# Sheet3.net
KiCad netlist of a schematic drawn in Altium Designer
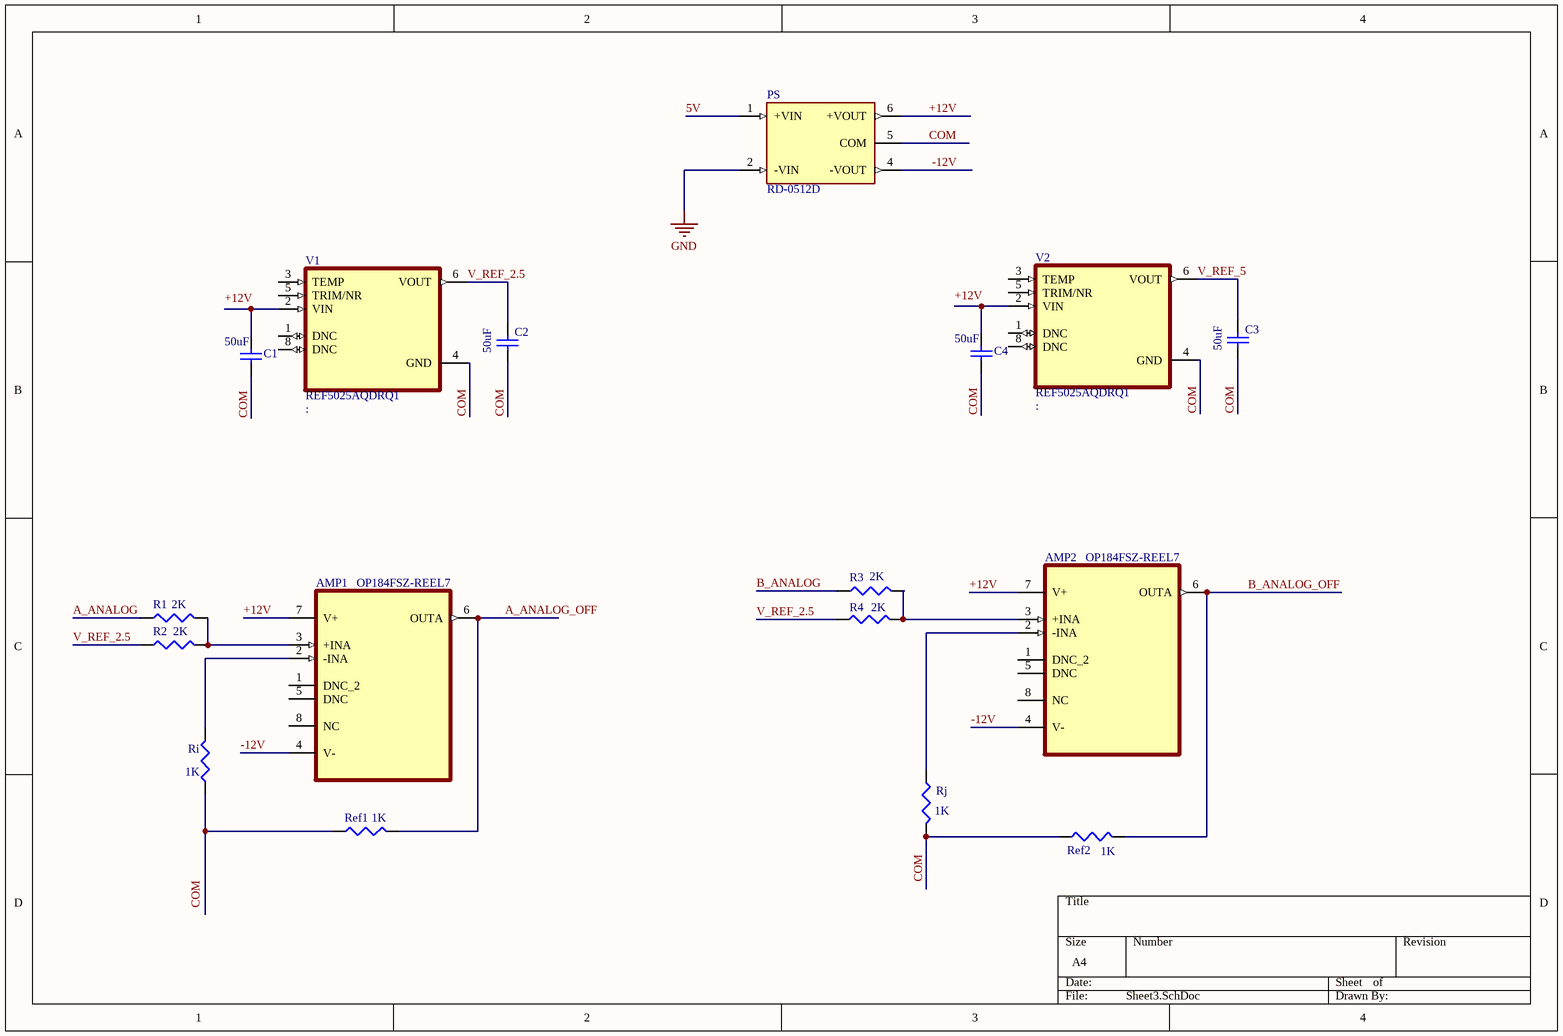
[diagram p0: Sheet3.SchDoc]

(export (version "E")
  (design (tool "Eeschema 10.0.6"))
  (components
    (comp (ref "AMP1")
      (value "OP184FSZ-REEL7")
      (footprint "SOIC127P600X175-8N")
      (description "General Purpose Amplifier 1 Circuit Rail-to-Rail 8-SOIC")
      (fields
        (field (name "MF") "Analog Devices")
        (field (name "DIGI-KEY_PART_NUMBER") "OP184FSZ-REEL7CT-ND")
      )
      (libsource (lib "altium-import") (part "root_0_OP184FSZ-REEL7_"))
    )
    (comp (ref "AMP2")
      (value "OP184FSZ-REEL7")
      (footprint "SOIC127P600X175-8N")
      (description "General Purpose Amplifier 1 Circuit Rail-to-Rail 8-SOIC")
      (fields
        (field (name "MF") "Analog Devices")
        (field (name "DIGI-KEY_PART_NUMBER") "OP184FSZ-REEL7CT-ND")
      )
      (libsource (lib "altium-import") (part "root_0_OP184FSZ-REEL7_"))
    )
    (comp (ref "C1")
      (value "50uF")
      (footprint "0402")
      (description "Capacitor (Semiconductor SIM Model)")
      (fields (field (name "PUBLISHER") "Altium Limited"))
      (libsource (lib "Miscellaneous Devices") (part "Cap Semi"))
    )
    (comp (ref "C2")
      (value "50uF")
      (footprint "0402")
      (description "Capacitor (Semiconductor SIM Model)")
      (fields (field (name "PUBLISHER") "Altium Limited"))
      (libsource (lib "Miscellaneous Devices") (part "Cap Semi"))
    )
    (comp (ref "C3")
      (value "50uF")
      (footprint "0402")
      (description "Capacitor (Semiconductor SIM Model)")
      (fields (field (name "PUBLISHER") "Altium Limited"))
      (libsource (lib "Miscellaneous Devices") (part "Cap Semi"))
    )
    (comp (ref "C4")
      (value "50uF")
      (footprint "0402")
      (description "Capacitor (Semiconductor SIM Model)")
      (fields (field (name "PUBLISHER") "Altium Limited"))
      (libsource (lib "Miscellaneous Devices") (part "Cap Semi"))
    )
    (comp (ref "PS")
      (value "RD-0512D")
      (footprint "CONV_RD-0512D")
      (description "2W DC/DC-Converter 'ECONOLINE' SIP7 1kV unreg")
      (fields (field (name "DIGI-KEY_PART_NUMBER") "945-1821-5-ND") (field (name "MF") "Recom Power"))
      (libsource (lib "altium-import") (part "root_0_RD-0512D_"))
    )
    (comp (ref "R1")
      (value "2K")
      (footprint "J1-0603")
      (description "Resistor")
      (fields (field (name "Comment") "Res3") (field (name "PUBLISHER") "Altium Limited"))
      (libsource (lib "Miscellaneous Devices") (part "Res3"))
    )
    (comp (ref "R2")
      (value "2K")
      (footprint "J1-0603")
      (description "Resistor")
      (fields (field (name "Comment") "Res3") (field (name "PUBLISHER") "Altium Limited"))
      (libsource (lib "Miscellaneous Devices") (part "Res3"))
    )
    (comp (ref "R3")
      (value "2K")
      (footprint "J1-0603")
      (description "Resistor")
      (fields (field (name "PUBLISHER") "Altium Limited"))
      (libsource (lib "Miscellaneous Devices") (part "Res3"))
    )
    (comp (ref "R4")
      (value "2K")
      (footprint "J1-0603")
      (description "Resistor")
      (fields (field (name "Comment") "Res3") (field (name "PUBLISHER") "Altium Limited"))
      (libsource (lib "Miscellaneous Devices") (part "Res3"))
    )
    (comp (ref "Ref1")
      (value "1K")
      (footprint "J1-0603")
      (description "Resistor")
      (fields (field (name "Comment") "Res3") (field (name "PUBLISHER") "Altium Limited"))
      (libsource (lib "Miscellaneous Devices") (part "Res3"))
    )
    (comp (ref "Ref2")
      (value "1K")
      (footprint "J1-0603")
      (description "Resistor")
      (fields (field (name "Comment") "Res3") (field (name "PUBLISHER") "Altium Limited"))
      (libsource (lib "Miscellaneous Devices") (part "Res3"))
    )
    (comp (ref "Ri")
      (value "1K")
      (footprint "J1-0603")
      (description "Resistor")
      (fields (field (name "Comment") "Res3") (field (name "PUBLISHER") "Altium Limited"))
      (libsource (lib "Miscellaneous Devices") (part "Res3"))
    )
    (comp (ref "Rj")
      (value "1K")
      (footprint "J1-0603")
      (description "Resistor")
      (fields (field (name "Comment") "Res3") (field (name "PUBLISHER") "Altium Limited"))
      (libsource (lib "Miscellaneous Devices") (part "Res3"))
    )
    (comp (ref "V1")
      (value "REF5025AQDRQ1")
      (footprint "SOIC127P599X175-8N")
      (description "Automotive, low-noise, very-low drift, precision 2.5-V series voltage reference 8-SOIC -40 to 125")
      (fields (field (name "MF") "Texas Instruments"))
      (libsource (lib "altium-import") (part "root_0_REF5025AQDRQ1_"))
    )
    (comp (ref "V2")
      (value "REF5025AQDRQ1")
      (footprint "SOIC127P599X175-8N")
      (description "Automotive, low-noise, very-low drift, precision 2.5-V series voltage reference 8-SOIC -40 to 125")
      (fields (field (name "MF") "Texas Instruments"))
      (libsource (lib "altium-import") (part "root_0_REF5025AQDRQ1_"))
    )
  )
  (nets
    (net (code "1") (name "/+12V") (class "Default")
      (node (ref "AMP1") (pin "7") (pinfunction "V+_7") (pintype "power_in"))
      (node (ref "AMP2") (pin "7") (pinfunction "V+_7") (pintype "power_in"))
      (node (ref "PS") (pin "6") (pinfunction "+VOUT_6") (pintype "output"))
    )
    (net (code "2") (name "/-12V") (class "Default")
      (node (ref "AMP1") (pin "4") (pinfunction "V-_4") (pintype "power_in"))
      (node (ref "AMP2") (pin "4") (pinfunction "V-_4") (pintype "power_in"))
      (node (ref "PS") (pin "4") (pinfunction "-VOUT_4") (pintype "output"))
    )
    (net (code "3") (name "/5V") (class "Default")
      (node (ref "PS") (pin "1") (pinfunction "+VIN_1") (pintype "input"))
    )
    (net (code "4") (name "/A_ANALOG") (class "Default")
      (node (ref "R1") (pin "1") (pinfunction "1_1") (pintype "passive"))
    )
    (net (code "5") (name "/A_ANALOG_OFF") (class "Default")
      (node (ref "AMP1") (pin "6") (pinfunction "OUTA_6") (pintype "output"))
      (node (ref "Ref1") (pin "2") (pinfunction "2_2") (pintype "passive"))
    )
    (net (code "6") (name "/B_ANALOG") (class "Default")
      (node (ref "R3") (pin "1") (pinfunction "1_1") (pintype "passive"))
    )
    (net (code "7") (name "/B_ANALOG_OFF") (class "Default")
      (node (ref "AMP2") (pin "6") (pinfunction "OUTA_6") (pintype "output"))
      (node (ref "Ref2") (pin "2") (pinfunction "2_2") (pintype "passive"))
    )
    (net (code "8") (name "/COM") (class "Default")
      (node (ref "C1") (pin "1") (pinfunction "1_1") (pintype "passive"))
      (node (ref "C2") (pin "1") (pinfunction "1_1") (pintype "passive"))
      (node (ref "C3") (pin "1") (pinfunction "1_1") (pintype "passive"))
      (node (ref "C4") (pin "1") (pinfunction "1_1") (pintype "passive"))
      (node (ref "PS") (pin "5") (pinfunction "COM_5") (pintype "power_in"))
      (node (ref "Ref2") (pin "1") (pinfunction "1_1") (pintype "passive"))
      (node (ref "Rj") (pin "2") (pinfunction "2_2") (pintype "passive"))
      (node (ref "V1") (pin "4") (pinfunction "GND_4") (pintype "power_in"))
      (node (ref "V2") (pin "4") (pinfunction "GND_4") (pintype "power_in"))
    )
    (net (code "9") (name "/V_REF_2.5") (class "Default")
      (node (ref "C2") (pin "2") (pinfunction "2_2") (pintype "passive"))
      (node (ref "R2") (pin "1") (pinfunction "1_1") (pintype "passive"))
      (node (ref "R4") (pin "1") (pinfunction "1_1") (pintype "passive"))
      (node (ref "V1") (pin "6") (pinfunction "VOUT_6") (pintype "output"))
    )
    (net (code "10") (name "/V_REF_5") (class "Default")
      (node (ref "C3") (pin "2") (pinfunction "2_2") (pintype "passive"))
      (node (ref "V2") (pin "6") (pinfunction "VOUT_6") (pintype "output"))
    )
    (net (code "11") (name "GND") (class "Default")
      (node (ref "PS") (pin "2") (pinfunction "-VIN_2") (pintype "input"))
    )
    (net (code "12") (name "Net-(AMP1-+INA)") (class "Default")
      (node (ref "AMP1") (pin "3") (pinfunction "+INA_3") (pintype "input"))
      (node (ref "R1") (pin "2") (pinfunction "2_2") (pintype "passive"))
      (node (ref "R2") (pin "2") (pinfunction "2_2") (pintype "passive"))
    )
    (net (code "13") (name "Net-(AMP1--INA)") (class "Default")
      (node (ref "AMP1") (pin "2") (pinfunction "-INA_2") (pintype "input"))
      (node (ref "Ri") (pin "2") (pinfunction "2_2") (pintype "passive"))
    )
    (net (code "14") (name "Net-(AMP2-+INA)") (class "Default")
      (node (ref "AMP2") (pin "3") (pinfunction "+INA_3") (pintype "input"))
      (node (ref "R3") (pin "2") (pinfunction "2_2") (pintype "passive"))
      (node (ref "R4") (pin "2") (pinfunction "2_2") (pintype "passive"))
    )
    (net (code "15") (name "Net-(AMP2--INA)") (class "Default")
      (node (ref "AMP2") (pin "2") (pinfunction "-INA_2") (pintype "input"))
      (node (ref "Rj") (pin "1") (pinfunction "1_1") (pintype "passive"))
    )
    (net (code "16") (name "Net-(Ref1-Pad1)") (class "Default")
      (node (ref "Ref1") (pin "1") (pinfunction "1_1") (pintype "passive"))
      (node (ref "Ri") (pin "1") (pinfunction "1_1") (pintype "passive"))
    )
    (net (code "17") (name "Net-(V1-VIN)") (class "Default")
      (node (ref "C1") (pin "2") (pinfunction "2_2") (pintype "passive"))
      (node (ref "V1") (pin "2") (pinfunction "VIN_2") (pintype "input"))
    )
    (net (code "18") (name "Net-(V2-VIN)") (class "Default")
      (node (ref "C4") (pin "2") (pinfunction "2_2") (pintype "passive"))
      (node (ref "V2") (pin "2") (pinfunction "VIN_2") (pintype "input"))
    )
    (net (code "19") (name "unconnected-(AMP1-DNC-Pad5)") (class "Default")
      (node (ref "AMP1") (pin "5") (pinfunction "DNC_5") (pintype "passive"))
    )
    (net (code "20") (name "unconnected-(AMP1-DNC_2-Pad1)") (class "Default")
      (node (ref "AMP1") (pin "1") (pinfunction "DNC_2_1") (pintype "passive"))
    )
    (net (code "21") (name "unconnected-(AMP1-NC-Pad8)") (class "Default")
      (node (ref "AMP1") (pin "8") (pinfunction "NC_8") (pintype "passive"))
    )
    (net (code "22") (name "unconnected-(AMP2-DNC-Pad5)") (class "Default")
      (node (ref "AMP2") (pin "5") (pinfunction "DNC_5") (pintype "passive"))
    )
    (net (code "23") (name "unconnected-(AMP2-DNC_2-Pad1)") (class "Default")
      (node (ref "AMP2") (pin "1") (pinfunction "DNC_2_1") (pintype "passive"))
    )
    (net (code "24") (name "unconnected-(AMP2-NC-Pad8)") (class "Default")
      (node (ref "AMP2") (pin "8") (pinfunction "NC_8") (pintype "passive"))
    )
    (net (code "25") (name "unconnected-(V1-DNC-Pad1)") (class "Default")
      (node (ref "V1") (pin "1") (pinfunction "DNC_1") (pintype "bidirectional"))
    )
    (net (code "26") (name "unconnected-(V1-DNC-Pad8)") (class "Default")
      (node (ref "V1") (pin "8") (pinfunction "DNC_8") (pintype "bidirectional"))
    )
    (net (code "27") (name "unconnected-(V1-TEMP-Pad3)") (class "Default")
      (node (ref "V1") (pin "3") (pinfunction "TEMP_3") (pintype "input"))
    )
    (net (code "28") (name "unconnected-(V1-TRIM{slash}NR-Pad5)") (class "Default")
      (node (ref "V1") (pin "5") (pinfunction "TRIM/NR_5") (pintype "input"))
    )
    (net (code "29") (name "unconnected-(V2-DNC-Pad1)") (class "Default")
      (node (ref "V2") (pin "1") (pinfunction "DNC_1") (pintype "bidirectional"))
    )
    (net (code "30") (name "unconnected-(V2-DNC-Pad8)") (class "Default")
      (node (ref "V2") (pin "8") (pinfunction "DNC_8") (pintype "bidirectional"))
    )
    (net (code "31") (name "unconnected-(V2-TEMP-Pad3)") (class "Default")
      (node (ref "V2") (pin "3") (pinfunction "TEMP_3") (pintype "input"))
    )
    (net (code "32") (name "unconnected-(V2-TRIM{slash}NR-Pad5)") (class "Default")
      (node (ref "V2") (pin "5") (pinfunction "TRIM/NR_5") (pintype "input"))
    )
  )
)
